# esp8266_5A.net
KiCad netlist of a schematic drawn in EAGLE
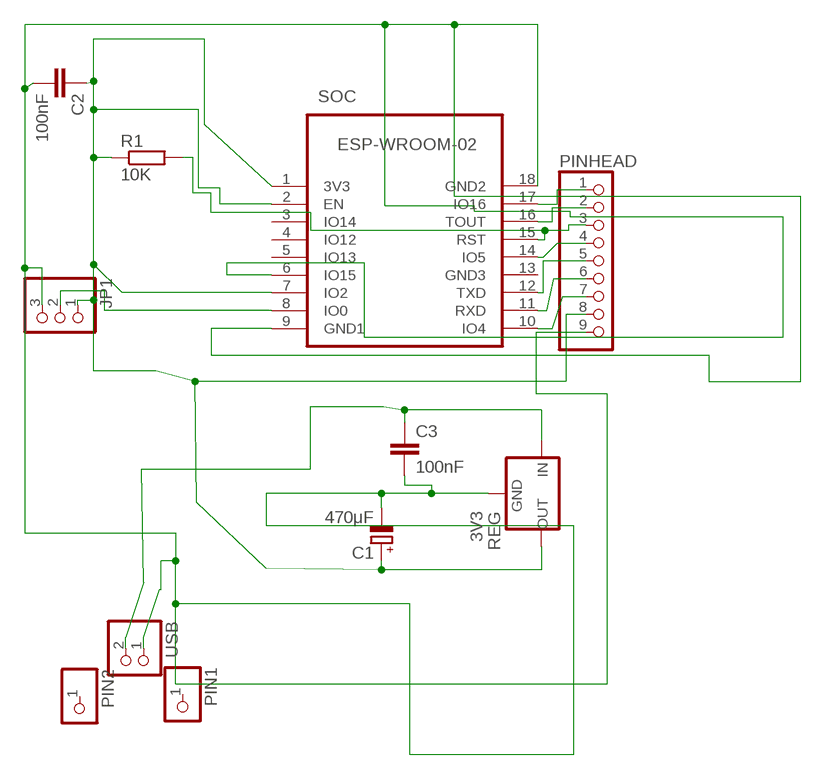
[diagram p0: schematic, sheet 1]

(export (version "E")
  (design (tool "Eeschema 10.0.6"))
  (components
    (comp (ref "C1")
      (value "470μF")
      (footprint "eagle-import:E2,5-7")
      (libsource (lib "eagle-import") (part "CPOL-EUE2.5-7"))
    )
    (comp (ref "C2")
      (value "100nF")
      (footprint "eagle-import:C0603")
      (libsource (lib "eagle-import") (part "C-EUC0603"))
    )
    (comp (ref "C3")
      (value "100nF")
      (footprint "eagle-import:C0603")
      (libsource (lib "eagle-import") (part "C-EUC0603"))
    )
    (comp (ref "JP1")
      (value "PINHD-1X3")
      (footprint "eagle-import:1X03")
      (libsource (lib "eagle-import") (part "PINHD-1X3"))
    )
    (comp (ref "PIN1")
      (value "PINHD-1X1")
      (footprint "eagle-import:1X01")
      (libsource (lib "eagle-import") (part "PINHD-1X1"))
    )
    (comp (ref "PIN2")
      (value "PINHD-1X1")
      (footprint "eagle-import:1X01")
      (libsource (lib "eagle-import") (part "PINHD-1X1"))
    )
    (comp (ref "PINHEAD")
      (value "PINHD-1X9")
      (footprint "eagle-import:1X09")
      (libsource (lib "eagle-import") (part "PINHD-1X9"))
    )
    (comp (ref "R1")
      (value "10K")
      (footprint "eagle-import:R0603")
      (libsource (lib "eagle-import") (part "R-EU_R0603"))
    )
    (comp (ref "REG")
      (value "3V3")
      (footprint "eagle-import:78XXS")
      (libsource (lib "eagle-import") (part "78XXS"))
    )
    (comp (ref "SOC")
      (value "ESP-WROOM-02")
      (footprint "eagle-import:FRONT-FACE-CP2")
      (libsource (lib "eagle-import") (part "ESP-WROOM-02-CP2FRONT"))
    )
    (comp (ref "USB")
      (value "PINHD-1X2")
      (footprint "eagle-import:1X02")
      (libsource (lib "eagle-import") (part "PINHD-1X2"))
    )
  )
  (nets
    (net (code "1") (name "Net-(C3-Pad1)") (class "Default")
      (node (ref "C3") (pin "1") (pinfunction "1_1") (pintype "passive"))
      (node (ref "REG") (pin "IN") (pinfunction "IN_IN") (pintype "input"))
      (node (ref "USB") (pin "2") (pinfunction "2_2") (pintype "passive"))
    )
    (net (code "2") (name "Net-(SOC-3V3)") (class "Default")
      (node (ref "C1") (pin "+") (pinfunction "+_+") (pintype "passive"))
      (node (ref "C2") (pin "1") (pinfunction "1_1") (pintype "passive"))
      (node (ref "JP1") (pin "1") (pinfunction "1_1") (pintype "passive"))
      (node (ref "PINHEAD") (pin "8") (pinfunction "8_8") (pintype "passive"))
      (node (ref "R1") (pin "1") (pinfunction "1_1") (pintype "passive"))
      (node (ref "REG") (pin "OUT") (pinfunction "OUT_OUT") (pintype "passive"))
      (node (ref "SOC") (pin "1") (pinfunction "3V3_1") (pintype "bidirectional"))
      (node (ref "SOC") (pin "2") (pinfunction "EN_2") (pintype "bidirectional"))
      (node (ref "SOC") (pin "7") (pinfunction "IO2_7") (pintype "bidirectional"))
    )
    (net (code "3") (name "Net-(SOC-GND1)") (class "Default")
      (node (ref "C1") (pin "-") (pinfunction "-_-") (pintype "passive"))
      (node (ref "C2") (pin "2") (pinfunction "2_2") (pintype "passive"))
      (node (ref "C3") (pin "2") (pinfunction "2_2") (pintype "passive"))
      (node (ref "JP1") (pin "3") (pinfunction "3_3") (pintype "passive"))
      (node (ref "PINHEAD") (pin "9") (pinfunction "9_9") (pintype "passive"))
      (node (ref "REG") (pin "GND") (pinfunction "GND_GND") (pintype "input"))
      (node (ref "SOC") (pin "18") (pinfunction "GND2_18") (pintype "bidirectional"))
      (node (ref "SOC") (pin "6") (pinfunction "IO15_6") (pintype "bidirectional"))
      (node (ref "SOC") (pin "9") (pinfunction "GND1_9") (pintype "bidirectional"))
      (node (ref "USB") (pin "1") (pinfunction "1_1") (pintype "passive"))
    )
    (net (code "4") (name "Net-(SOC-IO0)") (class "Default")
      (node (ref "JP1") (pin "2") (pinfunction "2_2") (pintype "passive"))
      (node (ref "SOC") (pin "8") (pinfunction "IO0_8") (pintype "bidirectional"))
    )
    (net (code "5") (name "Net-(SOC-IO4)") (class "Default")
      (node (ref "PINHEAD") (pin "7") (pinfunction "7_7") (pintype "passive"))
      (node (ref "SOC") (pin "10") (pinfunction "IO4_10") (pintype "bidirectional"))
    )
    (net (code "6") (name "Net-(SOC-IO5)") (class "Default")
      (node (ref "PINHEAD") (pin "4") (pinfunction "4_4") (pintype "passive"))
      (node (ref "SOC") (pin "14") (pinfunction "IO5_14") (pintype "bidirectional"))
    )
    (net (code "7") (name "Net-(SOC-IO16)") (class "Default")
      (node (ref "PINHEAD") (pin "1") (pinfunction "1_1") (pintype "passive"))
      (node (ref "SOC") (pin "17") (pinfunction "IO16_17") (pintype "bidirectional"))
    )
    (net (code "8") (name "Net-(SOC-RST)") (class "Default")
      (node (ref "PINHEAD") (pin "3") (pinfunction "3_3") (pintype "passive"))
      (node (ref "R1") (pin "2") (pinfunction "2_2") (pintype "passive"))
      (node (ref "SOC") (pin "15") (pinfunction "RST_15") (pintype "bidirectional"))
    )
    (net (code "9") (name "Net-(SOC-RXD)") (class "Default")
      (node (ref "PINHEAD") (pin "6") (pinfunction "6_6") (pintype "passive"))
      (node (ref "SOC") (pin "11") (pinfunction "RXD_11") (pintype "bidirectional"))
    )
    (net (code "10") (name "Net-(SOC-TOUT)") (class "Default")
      (node (ref "PINHEAD") (pin "2") (pinfunction "2_2") (pintype "passive"))
      (node (ref "SOC") (pin "16") (pinfunction "TOUT_16") (pintype "bidirectional"))
    )
    (net (code "11") (name "Net-(SOC-TXD)") (class "Default")
      (node (ref "PINHEAD") (pin "5") (pinfunction "5_5") (pintype "passive"))
      (node (ref "SOC") (pin "12") (pinfunction "TXD_12") (pintype "bidirectional"))
    )
    (net (code "12") (name "unconnected-(PIN1-Pad1)") (class "Default")
      (node (ref "PIN1") (pin "1") (pinfunction "1_1") (pintype "passive"))
    )
    (net (code "13") (name "unconnected-(PIN2-Pad1)") (class "Default")
      (node (ref "PIN2") (pin "1") (pinfunction "1_1") (pintype "passive"))
    )
    (net (code "14") (name "unconnected-(SOC-GND3-Pad13)") (class "Default")
      (node (ref "SOC") (pin "13") (pinfunction "GND3_13") (pintype "bidirectional"))
    )
    (net (code "15") (name "unconnected-(SOC-IO12-Pad4)") (class "Default")
      (node (ref "SOC") (pin "4") (pinfunction "IO12_4") (pintype "bidirectional"))
    )
    (net (code "16") (name "unconnected-(SOC-IO13-Pad5)") (class "Default")
      (node (ref "SOC") (pin "5") (pinfunction "IO13_5") (pintype "open_collector"))
    )
    (net (code "17") (name "unconnected-(SOC-IO14-Pad3)") (class "Default")
      (node (ref "SOC") (pin "3") (pinfunction "IO14_3") (pintype "bidirectional"))
    )
  )
)
